# PX_Header.net
KiCad netlist of a schematic drawn in Altium Designer
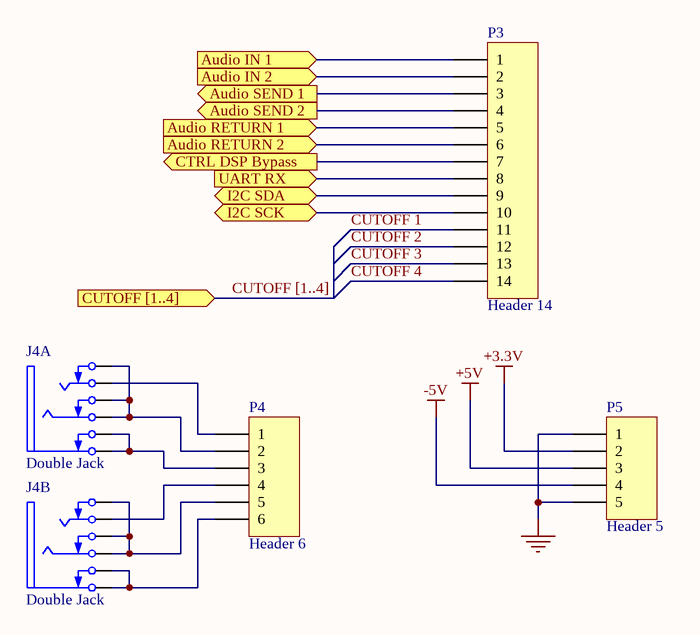
[diagram p0: PX_Header.SchDoc]

(export (version "E")
  (design (tool "Eeschema 10.0.6"))
  (components
    (comp (ref "J4")
      (value "Double Jack")
      (description "Dual Jack stereo bypassed")
      (libsource (lib "FilterPoC") (part "Dual TRS Jack Bypassed"))
    )
    (comp (ref "P3")
      (value "Header 14")
      (description "Header, 14-Pin")
      (libsource (lib "Miscellaneous Connectors") (part "Header 14"))
    )
    (comp (ref "P4")
      (value "Header 6")
      (description "Header, 6-Pin")
      (libsource (lib "Miscellaneous Connectors") (part "Header 6"))
    )
    (comp (ref "P5")
      (value "Header 5")
      (description "Header, 5-Pin")
      (libsource (lib "Miscellaneous Connectors") (part "Header 5"))
    )
  )
  (nets
    (net (code "1") (name "+3.3V") (class "Default")
      (node (ref "P5") (pin "2") (pinfunction "2_2") (pintype "passive"))
    )
    (net (code "2") (name "+5V") (class "Default")
      (node (ref "P5") (pin "3") (pinfunction "3_3") (pintype "passive"))
    )
    (net (code "3") (name "-5V") (class "Default")
      (node (ref "P5") (pin "4") (pinfunction "4_4") (pintype "passive"))
    )
    (net (code "4") (name "/Audio IN 1") (class "Default")
      (node (ref "P3") (pin "1") (pinfunction "1_1") (pintype "passive"))
    )
    (net (code "5") (name "/Audio IN 2") (class "Default")
      (node (ref "P3") (pin "2") (pinfunction "2_2") (pintype "passive"))
    )
    (net (code "6") (name "/Audio RETURN 1") (class "Default")
      (node (ref "P3") (pin "5") (pinfunction "5_5") (pintype "passive"))
    )
    (net (code "7") (name "/Audio RETURN 2") (class "Default")
      (node (ref "P3") (pin "6") (pinfunction "6_6") (pintype "passive"))
    )
    (net (code "8") (name "/Audio SEND 1") (class "Default")
      (node (ref "P3") (pin "3") (pinfunction "3_3") (pintype "passive"))
    )
    (net (code "9") (name "/Audio SEND 2") (class "Default")
      (node (ref "P3") (pin "4") (pinfunction "4_4") (pintype "passive"))
    )
    (net (code "10") (name "/CTRL DSP Bypass") (class "Default")
      (node (ref "P3") (pin "7") (pinfunction "7_7") (pintype "passive"))
    )
    (net (code "11") (name "/CUTOFF 1") (class "Default")
      (node (ref "P3") (pin "11") (pinfunction "11_11") (pintype "passive"))
    )
    (net (code "12") (name "/CUTOFF 2") (class "Default")
      (node (ref "P3") (pin "12") (pinfunction "12_12") (pintype "passive"))
    )
    (net (code "13") (name "/CUTOFF 3") (class "Default")
      (node (ref "P3") (pin "13") (pinfunction "13_13") (pintype "passive"))
    )
    (net (code "14") (name "/CUTOFF 4") (class "Default")
      (node (ref "P3") (pin "14") (pinfunction "14_14") (pintype "passive"))
    )
    (net (code "15") (name "/I2C SCK") (class "Default")
      (node (ref "P3") (pin "10") (pinfunction "10_10") (pintype "passive"))
    )
    (net (code "16") (name "/I2C SDA") (class "Default")
      (node (ref "P3") (pin "9") (pinfunction "9_9") (pintype "passive"))
    )
    (net (code "17") (name "/UART RX") (class "Default")
      (node (ref "P3") (pin "8") (pinfunction "8_8") (pintype "passive"))
    )
    (net (code "19") (name "GND") (class "Default")
      (node (ref "P5") (pin "1") (pinfunction "1_1") (pintype "passive"))
      (node (ref "P5") (pin "5") (pinfunction "5_5") (pintype "passive"))
    )
    (net (code "20") (name "Net-(J4A-R)") (class "Default")
      (node (ref "J4") (pin "11") (pinfunction "R_11") (pintype "passive"))
      (node (ref "J4") (pin "8") (pinfunction "RB_8") (pintype "passive"))
      (node (ref "J4") (pin "9") (pinfunction "TB_9") (pintype "passive"))
      (node (ref "P4") (pin "2") (pinfunction "2_2") (pintype "passive"))
    )
    (net (code "21") (name "Net-(J4A-S)") (class "Default")
      (node (ref "J4") (pin "10") (pinfunction "S_10") (pintype "power_in"))
      (node (ref "J4") (pin "7") (pinfunction "SB_7") (pintype "passive"))
      (node (ref "P4") (pin "3") (pinfunction "3_3") (pintype "passive"))
    )
    (net (code "22") (name "Net-(J4A-T)") (class "Default")
      (node (ref "J4") (pin "12") (pinfunction "T_12") (pintype "passive"))
      (node (ref "P4") (pin "1") (pinfunction "1_1") (pintype "passive"))
    )
    (net (code "23") (name "Net-(J4B-R)") (class "Default")
      (node (ref "J4") (pin "2") (pinfunction "RB_2") (pintype "passive"))
      (node (ref "J4") (pin "3") (pinfunction "TB_3") (pintype "passive"))
      (node (ref "J4") (pin "5") (pinfunction "R_5") (pintype "passive"))
      (node (ref "P4") (pin "5") (pinfunction "5_5") (pintype "passive"))
    )
    (net (code "24") (name "Net-(J4B-S)") (class "Default")
      (node (ref "J4") (pin "1") (pinfunction "SB_1") (pintype "passive"))
      (node (ref "J4") (pin "4") (pinfunction "S_4") (pintype "power_in"))
      (node (ref "P4") (pin "6") (pinfunction "6_6") (pintype "passive"))
    )
    (net (code "25") (name "Net-(J4B-T)") (class "Default")
      (node (ref "J4") (pin "6") (pinfunction "T_6") (pintype "passive"))
      (node (ref "P4") (pin "4") (pinfunction "4_4") (pintype "passive"))
    )
  )
)
